# HalfBridge.net
KiCad netlist of a schematic drawn in Altium Designer
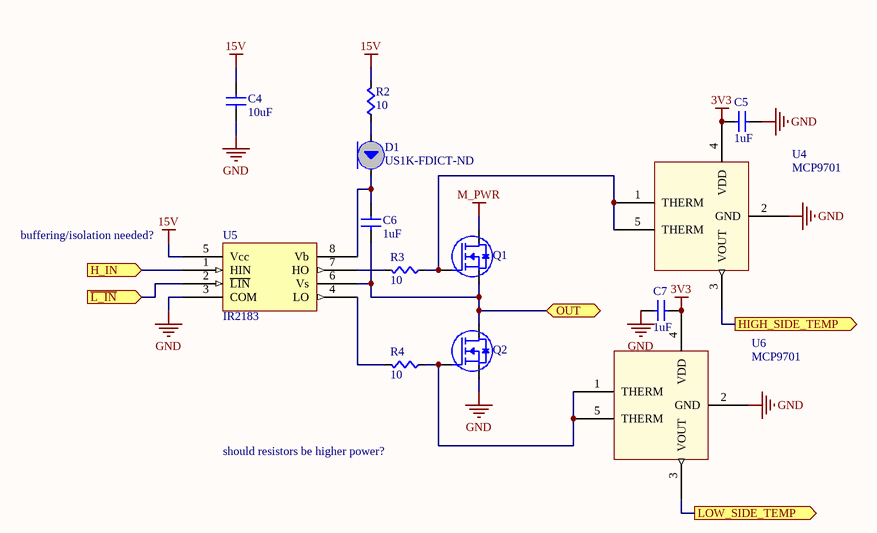
[diagram p0: HalfBridge.SchDoc]

(export (version "E")
  (design (tool "Eeschema 10.0.6"))
  (components
    (comp (ref "C4")
      (value "10uF")
      (footprint "CAPC0603")
      (fields (field (name "Comment") "Cap"))
      (libsource (lib "Passives") (part "Cap"))
    )
    (comp (ref "C5")
      (value "1uF")
      (footprint "CAPC0603")
      (fields (field (name "Comment") "Cap"))
      (libsource (lib "Passives") (part "Cap"))
    )
    (comp (ref "C6")
      (value "1uF")
      (footprint "CAPC0603")
      (fields (field (name "Comment") "Cap"))
      (libsource (lib "Passives") (part "Cap"))
    )
    (comp (ref "C7")
      (value "1uF")
      (footprint "CAPC0603")
      (fields (field (name "Comment") "Cap"))
      (libsource (lib "Passives") (part "Cap"))
    )
    (comp (ref "D1")
      (value "US1K-13-F")
      (footprint "US1K-13-F")
      (description "1.0A SURFACE MOUNT ULTRA-FAST RECTIFIER")
      (fields (field (name "SUPPLIER PART NUMBER 1") "US1K-FDICT-ND"))
      (libsource (lib "Semiconductors") (part "US1K-13-F"))
    )
    (comp (ref "Q1")
      (value "IRLU3636PbF")
      (footprint "IRLU3636PbF")
      (description "HEXFET Power MOSFET")
      (libsource (lib "Semiconductors") (part "IRLU3636PbF"))
    )
    (comp (ref "Q2")
      (value "IRLU3636PbF")
      (footprint "IRLU3636PbF")
      (description "HEXFET Power MOSFET")
      (libsource (lib "Semiconductors") (part "IRLU3636PbF"))
    )
    (comp (ref "R2")
      (value "10")
      (footprint "RES0603")
      (fields (field (name "Comment") "Res"))
      (libsource (lib "Passives") (part "Res"))
    )
    (comp (ref "R3")
      (value "10")
      (footprint "RES0603")
      (fields (field (name "Comment") "Res"))
      (libsource (lib "Passives") (part "Res"))
    )
    (comp (ref "R4")
      (value "10")
      (footprint "RES0603")
      (fields (field (name "Comment") "Res"))
      (libsource (lib "Passives") (part "Res"))
    )
    (comp (ref "U4")
      (value "MCP9701")
      (footprint "MCP9701AT-E/LT")
      (description "Low-Power Linear Active Thermistor ICs")
      (libsource (lib "ICs") (part "MCP9701AT-E/LT"))
    )
    (comp (ref "U5")
      (value "IR2183")
      (footprint "IR2183S")
      (description "Half-Bridge Driver")
      (libsource (lib "ICs") (part "IR2183"))
    )
    (comp (ref "U6")
      (value "MCP9701")
      (footprint "MCP9701AT-E/LT")
      (description "Low-Power Linear Active Thermistor ICs")
      (libsource (lib "ICs") (part "MCP9701AT-E/LT"))
    )
  )
  (nets
    (net (code "1") (name "/HIGH_SIDE_TEMP") (class "Default")
      (node (ref "U4") (pin "3") (pinfunction "VOUT_3") (pintype "output"))
    )
    (net (code "2") (name "/H_IN") (class "Default")
      (node (ref "U5") (pin "1") (pinfunction "HIN_1") (pintype "input"))
    )
    (net (code "3") (name "/LOW_SIDE_TEMP") (class "Default")
      (node (ref "U6") (pin "3") (pinfunction "VOUT_3") (pintype "output"))
    )
    (net (code "4") (name "/OUT") (class "Default")
      (node (ref "C6") (pin "2") (pinfunction "B_2") (pintype "passive"))
      (node (ref "Q1") (pin "S") (pinfunction "S_S") (pintype "passive"))
      (node (ref "Q2") (pin "D") (pinfunction "D_D") (pintype "passive"))
      (node (ref "U5") (pin "6") (pinfunction "Vs_6") (pintype "power_in"))
    )
    (net (code "5") (name "/~{L_IN}") (class "Default")
      (node (ref "U5") (pin "2") (pinfunction "~{LIN}_2") (pintype "input"))
    )
    (net (code "6") (name "3V3") (class "Default")
      (node (ref "C5") (pin "2") (pinfunction "B_2") (pintype "passive"))
      (node (ref "C7") (pin "1") (pinfunction "A_1") (pintype "passive"))
      (node (ref "U4") (pin "4") (pinfunction "VDD_4") (pintype "power_in"))
      (node (ref "U6") (pin "4") (pinfunction "VDD_4") (pintype "power_in"))
    )
    (net (code "7") (name "15V") (class "Default")
      (node (ref "C4") (pin "1") (pinfunction "A_1") (pintype "passive"))
      (node (ref "R2") (pin "1") (pinfunction "A_1") (pintype "passive"))
      (node (ref "U5") (pin "5") (pinfunction "Vcc_5") (pintype "power_in"))
    )
    (net (code "8") (name "GND") (class "Default")
      (node (ref "C4") (pin "2") (pinfunction "B_2") (pintype "passive"))
      (node (ref "C5") (pin "1") (pinfunction "A_1") (pintype "passive"))
      (node (ref "C7") (pin "2") (pinfunction "B_2") (pintype "passive"))
      (node (ref "Q2") (pin "S") (pinfunction "S_S") (pintype "passive"))
      (node (ref "U4") (pin "2") (pinfunction "GND_2") (pintype "power_in"))
      (node (ref "U5") (pin "3") (pinfunction "COM_3") (pintype "power_in"))
      (node (ref "U6") (pin "2") (pinfunction "GND_2") (pintype "power_in"))
    )
    (net (code "9") (name "M_PWR") (class "Default")
      (node (ref "Q1") (pin "D") (pinfunction "D_D") (pintype "passive"))
    )
    (net (code "10") (name "Net-(C6-A)") (class "Default")
      (node (ref "C6") (pin "1") (pinfunction "A_1") (pintype "passive"))
      (node (ref "D1") (pin "C") (pinfunction "C_C") (pintype "passive"))
      (node (ref "U5") (pin "8") (pinfunction "Vb_8") (pintype "passive"))
    )
    (net (code "11") (name "Net-(R2-B)") (class "Default")
      (node (ref "D1") (pin "A") (pinfunction "A_A") (pintype "passive"))
      (node (ref "R2") (pin "2") (pinfunction "B_2") (pintype "passive"))
    )
    (net (code "12") (name "Net-(R3-A)") (class "Default")
      (node (ref "R3") (pin "1") (pinfunction "A_1") (pintype "passive"))
      (node (ref "U5") (pin "7") (pinfunction "HO_7") (pintype "output"))
    )
    (net (code "13") (name "Net-(R3-B)") (class "Default")
      (node (ref "Q1") (pin "G") (pinfunction "G_G") (pintype "passive"))
      (node (ref "R3") (pin "2") (pinfunction "B_2") (pintype "passive"))
      (node (ref "U4") (pin "1") (pinfunction "THERM_1") (pintype "passive"))
      (node (ref "U4") (pin "5") (pinfunction "THERM_5") (pintype "passive"))
    )
    (net (code "14") (name "Net-(R4-A)") (class "Default")
      (node (ref "R4") (pin "1") (pinfunction "A_1") (pintype "passive"))
      (node (ref "U5") (pin "4") (pinfunction "LO_4") (pintype "output"))
    )
    (net (code "15") (name "Net-(R4-B)") (class "Default")
      (node (ref "Q2") (pin "G") (pinfunction "G_G") (pintype "passive"))
      (node (ref "R4") (pin "2") (pinfunction "B_2") (pintype "passive"))
      (node (ref "U6") (pin "1") (pinfunction "THERM_1") (pintype "passive"))
      (node (ref "U6") (pin "5") (pinfunction "THERM_5") (pintype "passive"))
    )
  )
)
